# OurEDA-P1K_sensor.net
KiCad netlist of a schematic drawn in Altium Designer
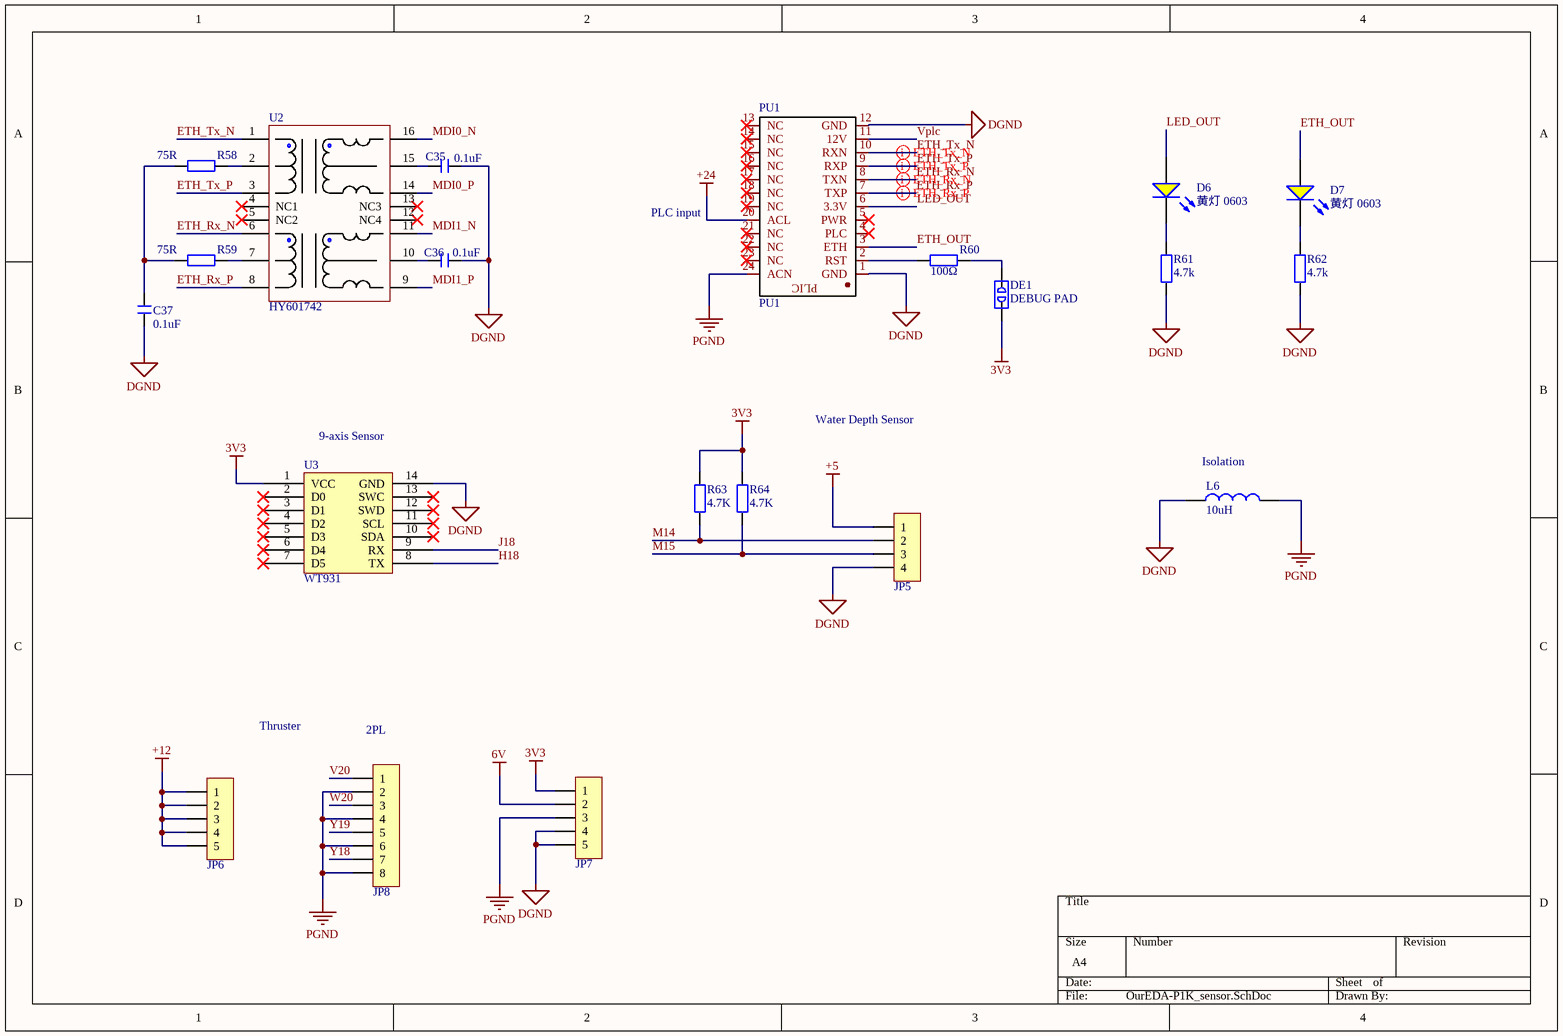
[diagram p0: OurEDA-P1K_sensor.SchDoc]

(export (version "E")
  (design (tool "Eeschema 10.0.6"))
  (components
    (comp (ref "C35")
      (value "0.1uF")
      (footprint "C 0603_L")
      (description "无极性贴片电容")
      (fields (field (name "版权归属") "源创客"))
      (libsource (lib "3.1   - 电阻-电容-电感") (part "C"))
    )
    (comp (ref "C36")
      (value "0.1uF")
      (footprint "C 0603_L")
      (description "无极性贴片电容")
      (fields (field (name "版权归属") "源创客"))
      (libsource (lib "3.1   - 电阻-电容-电感") (part "C"))
    )
    (comp (ref "C37")
      (value "0.1uF")
      (footprint "C 0603_L")
      (description "无极性贴片电容")
      (fields (field (name "版权归属") "源创客"))
      (libsource (lib "3.1   - 电阻-电容-电感") (part "C"))
    )
    (comp (ref "D6")
      (value "黄灯 0603")
      (footprint "0603_LED_S1")
      (description "发光二极管")
      (libsource (lib "Miscellaneous Devices LC") (part "0603 黄灯"))
    )
    (comp (ref "D7")
      (value "黄灯 0603")
      (footprint "0603_LED_S1")
      (description "发光二极管")
      (libsource (lib "Miscellaneous Devices LC") (part "0603 黄灯"))
    )
    (comp (ref "DE1")
      (value "DEBUG PAD")
      (footprint "DEBUG_A")
      (description "调试断点焊盘")
      (fields (field (name "版权归属") "源创客"))
      (libsource (lib "15.1 - 未分类器件") (part "DEBUG"))
    )
    (comp (ref "JP5")
      (value "HDR-1X4")
      (footprint "MX 1.25-LI-4P")
      (description "4P接插件")
      (fields (field (name "版权归属") "源创客"))
      (libsource (lib "4.2   - 接插件-脚距1.25") (part "Header 4"))
    )
    (comp (ref "JP6")
      (value "HDR-1X5")
      (footprint "KF128-5.08-5P")
      (description "5P接插件")
      (fields (field (name "版权归属") "源创客"))
      (libsource (lib "4.10 - 接插件-脚距5.08") (part "Header 5"))
    )
    (comp (ref "JP7")
      (value "HDR-1X5")
      (footprint "KF128-5.08-5P")
      (description "5P接插件")
      (fields (field (name "版权归属") "源创客"))
      (libsource (lib "4.10 - 接插件-脚距5.08") (part "Header 5"))
    )
    (comp (ref "JP8")
      (value "HDR-1X8")
      (footprint "KF128-5.08-8P")
      (description "8P接插件")
      (fields (field (name "版权归属") "源创客"))
      (libsource (lib "4.10 - 接插件-脚距5.08") (part "Header 8"))
    )
    (comp (ref "L6")
      (value "10uH")
      (footprint "L 0805")
      (description "小功率贴片电感")
      (fields (field (name "版权归属") "源创客"))
      (libsource (lib "3.1   - 电阻-电容-电感") (part "L"))
    )
    (comp (ref "PU1") (value "PU1") (footprint "LW-MPA223A") (libsource (lib "SchLib1") (part "LW-MPA223A")))
    (comp (ref "R58")
      (value "75R")
      (footprint "0603_R")
      (description "贴片电阻")
      (libsource (lib "Miscellaneous Devices LC") (part "0603 330Ω (3300) 1%"))
    )
    (comp (ref "R59")
      (value "75R")
      (footprint "0603_R")
      (description "贴片电阻")
      (libsource (lib "Miscellaneous Devices LC") (part "0603 330Ω (3300) 1%"))
    )
    (comp (ref "R60")
      (value "100Ω")
      (footprint "0603_R")
      (description "贴片电阻")
      (libsource (lib "Miscellaneous Devices LC") (part "0603 330Ω (3300) 1%"))
    )
    (comp (ref "R61")
      (value "4.7k")
      (footprint "R 0603_L")
      (description "贴片电阻")
      (fields (field (name "版权归属") "源创客"))
      (libsource (lib "3.1   - 电阻-电容-电感") (part "R"))
    )
    (comp (ref "R62")
      (value "4.7k")
      (footprint "R 0603_L")
      (description "贴片电阻")
      (fields (field (name "版权归属") "源创客"))
      (libsource (lib "3.1   - 电阻-电容-电感") (part "R"))
    )
    (comp (ref "R63")
      (value "4.7K")
      (footprint "R 0603_L")
      (description "贴片电阻")
      (fields (field (name "版权归属") "源创客"))
      (libsource (lib "3.1   - 电阻-电容-电感") (part "R"))
    )
    (comp (ref "R64")
      (value "4.7K")
      (footprint "R 0603_L")
      (description "贴片电阻")
      (fields (field (name "版权归属") "源创客"))
      (libsource (lib "3.1   - 电阻-电容-电感") (part "R"))
    )
    (comp (ref "U2")
      (value "HY601742")
      (footprint "SOP-16_350mil")
      (description "以太网变压器")
      (libsource (lib "MySchLib") (part "HY601742_1"))
    )
    (comp (ref "U3")
      (value "WT931")
      (footprint "WT931")
      (description "维特智能WT931九轴模块")
      (libsource (lib "MySchLib") (part "WT931"))
    )
  )
  (nets
    (net (code "1") (name "+5") (class "Default")
      (node (ref "JP5") (pin "1") (pinfunction "1_1") (pintype "passive"))
    )
    (net (code "2") (name "+12") (class "Default")
      (node (ref "JP6") (pin "1") (pinfunction "1_1") (pintype "passive"))
      (node (ref "JP6") (pin "2") (pinfunction "2_2") (pintype "passive"))
      (node (ref "JP6") (pin "3") (pinfunction "3_3") (pintype "passive"))
      (node (ref "JP6") (pin "4") (pinfunction "4_4") (pintype "passive"))
      (node (ref "JP6") (pin "5") (pinfunction "5_5") (pintype "passive"))
    )
    (net (code "3") (name "+24") (class "Default")
      (node (ref "PU1") (pin "20") (pinfunction "ACL_20") (pintype "passive"))
    )
    (net (code "4") (name "/ETH_OUT") (class "Default")
      (node (ref "D7") (pin "A") (pinfunction "A_A") (pintype "passive"))
      (node (ref "PU1") (pin "3") (pinfunction "ETH_3") (pintype "passive"))
    )
    (net (code "5") (name "/ETH_Rx_N") (class "Default")
      (node (ref "PU1") (pin "8") (pinfunction "TXN_8") (pintype "passive"))
      (node (ref "U2") (pin "6") (pinfunction "RD+_6") (pintype "passive"))
    )
    (net (code "6") (name "/ETH_Rx_P") (class "Default")
      (node (ref "PU1") (pin "7") (pinfunction "TXP_7") (pintype "passive"))
      (node (ref "U2") (pin "8") (pinfunction "RD-_8") (pintype "passive"))
    )
    (net (code "7") (name "/ETH_Tx_N") (class "Default")
      (node (ref "PU1") (pin "10") (pinfunction "RXN_10") (pintype "passive"))
      (node (ref "U2") (pin "1") (pinfunction "TD+_1") (pintype "passive"))
    )
    (net (code "8") (name "/ETH_Tx_P") (class "Default")
      (node (ref "PU1") (pin "9") (pinfunction "RXP_9") (pintype "passive"))
      (node (ref "U2") (pin "3") (pinfunction "TD-_3") (pintype "passive"))
    )
    (net (code "9") (name "/H18") (class "Default")
      (node (ref "U3") (pin "8") (pinfunction "TX_8") (pintype "passive"))
    )
    (net (code "10") (name "/J18") (class "Default")
      (node (ref "U3") (pin "9") (pinfunction "RX_9") (pintype "passive"))
    )
    (net (code "11") (name "/LED_OUT") (class "Default")
      (node (ref "D6") (pin "A") (pinfunction "A_A") (pintype "passive"))
      (node (ref "PU1") (pin "6") (pinfunction "3.3V_6") (pintype "passive"))
    )
    (net (code "12") (name "/M14") (class "Default")
      (node (ref "JP5") (pin "2") (pinfunction "2_2") (pintype "passive"))
      (node (ref "R63") (pin "1") (pinfunction "1_1") (pintype "passive"))
    )
    (net (code "13") (name "/M15") (class "Default")
      (node (ref "JP5") (pin "3") (pinfunction "3_3") (pintype "passive"))
      (node (ref "R64") (pin "1") (pinfunction "1_1") (pintype "passive"))
    )
    (net (code "14") (name "/MDI0_N") (class "Default")
      (node (ref "U2") (pin "16") (pinfunction "TX+_16") (pintype "passive"))
    )
    (net (code "15") (name "/MDI0_P") (class "Default")
      (node (ref "U2") (pin "14") (pinfunction "TX-_14") (pintype "passive"))
    )
    (net (code "16") (name "/MDI1_N") (class "Default")
      (node (ref "U2") (pin "11") (pinfunction "RX+_11") (pintype "passive"))
    )
    (net (code "17") (name "/MDI1_P") (class "Default")
      (node (ref "U2") (pin "9") (pinfunction "RX-_9") (pintype "passive"))
    )
    (net (code "18") (name "/V20") (class "Default")
      (node (ref "JP8") (pin "1") (pinfunction "1_1") (pintype "passive"))
    )
    (net (code "19") (name "/Vplc") (class "Default")
      (node (ref "PU1") (pin "11") (pinfunction "12V_11") (pintype "passive"))
    )
    (net (code "20") (name "/W20") (class "Default")
      (node (ref "JP8") (pin "3") (pinfunction "3_3") (pintype "passive"))
    )
    (net (code "21") (name "/Y18") (class "Default")
      (node (ref "JP8") (pin "7") (pinfunction "7_7") (pintype "passive"))
    )
    (net (code "22") (name "/Y19") (class "Default")
      (node (ref "JP8") (pin "5") (pinfunction "5_5") (pintype "passive"))
    )
    (net (code "23") (name "3V3") (class "Default")
      (node (ref "DE1") (pin "1") (pinfunction "1_1") (pintype "passive"))
      (node (ref "JP7") (pin "1") (pinfunction "1_1") (pintype "passive"))
      (node (ref "R63") (pin "2") (pinfunction "2_2") (pintype "passive"))
      (node (ref "R64") (pin "2") (pinfunction "2_2") (pintype "passive"))
      (node (ref "U3") (pin "1") (pinfunction "VCC_1") (pintype "passive"))
    )
    (net (code "24") (name "6V") (class "Default")
      (node (ref "JP7") (pin "2") (pinfunction "2_2") (pintype "passive"))
    )
    (net (code "25") (name "DGND") (class "Default")
      (node (ref "C35") (pin "1") (pinfunction "1_1") (pintype "passive"))
      (node (ref "C36") (pin "1") (pinfunction "1_1") (pintype "passive"))
      (node (ref "C37") (pin "1") (pinfunction "1_1") (pintype "passive"))
      (node (ref "JP5") (pin "4") (pinfunction "4_4") (pintype "passive"))
      (node (ref "JP7") (pin "4") (pinfunction "4_4") (pintype "passive"))
      (node (ref "JP7") (pin "5") (pinfunction "5_5") (pintype "passive"))
      (node (ref "L6") (pin "1") (pinfunction "1_1") (pintype "passive"))
      (node (ref "PU1") (pin "1") (pinfunction "GND_1") (pintype "passive"))
      (node (ref "PU1") (pin "12") (pinfunction "GND_12") (pintype "passive"))
      (node (ref "R61") (pin "1") (pinfunction "1_1") (pintype "passive"))
      (node (ref "R62") (pin "1") (pinfunction "1_1") (pintype "passive"))
      (node (ref "U3") (pin "14") (pinfunction "GND_14") (pintype "passive"))
    )
    (net (code "26") (name "Net-(C37-Pad2)") (class "Default")
      (node (ref "C37") (pin "2") (pinfunction "2_2") (pintype "passive"))
      (node (ref "R58") (pin "2") (pinfunction "2_2") (pintype "passive"))
      (node (ref "R59") (pin "2") (pinfunction "2_2") (pintype "passive"))
    )
    (net (code "27") (name "Net-(D6-PadK)") (class "Default")
      (node (ref "D6") (pin "K") (pinfunction "K_K") (pintype "passive"))
      (node (ref "R61") (pin "2") (pinfunction "2_2") (pintype "passive"))
    )
    (net (code "28") (name "Net-(D7-PadK)") (class "Default")
      (node (ref "D7") (pin "K") (pinfunction "K_K") (pintype "passive"))
      (node (ref "R62") (pin "2") (pinfunction "2_2") (pintype "passive"))
    )
    (net (code "29") (name "Net-(DE1-Pad2)") (class "Default")
      (node (ref "DE1") (pin "2") (pinfunction "2_2") (pintype "passive"))
      (node (ref "R60") (pin "1") (pinfunction "1_1") (pintype "passive"))
    )
    (net (code "30") (name "Net-(PU1-RST)") (class "Default")
      (node (ref "PU1") (pin "2") (pinfunction "RST_2") (pintype "passive"))
      (node (ref "R60") (pin "2") (pinfunction "2_2") (pintype "passive"))
    )
    (net (code "31") (name "Net-(U2-CM1)") (class "Default")
      (node (ref "C35") (pin "2") (pinfunction "2_2") (pintype "passive"))
      (node (ref "U2") (pin "15") (pinfunction "CM1_15") (pintype "passive"))
    )
    (net (code "32") (name "Net-(U2-CM2)") (class "Default")
      (node (ref "C36") (pin "2") (pinfunction "2_2") (pintype "passive"))
      (node (ref "U2") (pin "10") (pinfunction "CM2_10") (pintype "passive"))
    )
    (net (code "33") (name "Net-(U2-CT1)") (class "Default")
      (node (ref "R58") (pin "1") (pinfunction "1_1") (pintype "passive"))
      (node (ref "U2") (pin "2") (pinfunction "CT1_2") (pintype "passive"))
    )
    (net (code "34") (name "Net-(U2-CT2)") (class "Default")
      (node (ref "R59") (pin "1") (pinfunction "1_1") (pintype "passive"))
      (node (ref "U2") (pin "7") (pinfunction "CT2_7") (pintype "passive"))
    )
    (net (code "35") (name "PGND") (class "Default")
      (node (ref "JP7") (pin "3") (pinfunction "3_3") (pintype "passive"))
      (node (ref "JP8") (pin "2") (pinfunction "2_2") (pintype "passive"))
      (node (ref "JP8") (pin "4") (pinfunction "4_4") (pintype "passive"))
      (node (ref "JP8") (pin "6") (pinfunction "6_6") (pintype "passive"))
      (node (ref "JP8") (pin "8") (pinfunction "8_8") (pintype "passive"))
      (node (ref "L6") (pin "2") (pinfunction "2_2") (pintype "passive"))
      (node (ref "PU1") (pin "24") (pinfunction "ACN_24") (pintype "passive"))
    )
    (net (code "36") (name "unconnected-(PU1-NC-Pad13)") (class "Default")
      (node (ref "PU1") (pin "13") (pinfunction "NC_13") (pintype "passive+no_connect"))
    )
    (net (code "37") (name "unconnected-(PU1-NC-Pad14)") (class "Default")
      (node (ref "PU1") (pin "14") (pinfunction "NC_14") (pintype "passive+no_connect"))
    )
    (net (code "38") (name "unconnected-(PU1-NC-Pad15)") (class "Default")
      (node (ref "PU1") (pin "15") (pinfunction "NC_15") (pintype "passive+no_connect"))
    )
    (net (code "39") (name "unconnected-(PU1-NC-Pad16)") (class "Default")
      (node (ref "PU1") (pin "16") (pinfunction "NC_16") (pintype "passive+no_connect"))
    )
    (net (code "40") (name "unconnected-(PU1-NC-Pad17)") (class "Default")
      (node (ref "PU1") (pin "17") (pinfunction "NC_17") (pintype "passive+no_connect"))
    )
    (net (code "41") (name "unconnected-(PU1-NC-Pad18)") (class "Default")
      (node (ref "PU1") (pin "18") (pinfunction "NC_18") (pintype "passive+no_connect"))
    )
    (net (code "42") (name "unconnected-(PU1-NC-Pad19)") (class "Default")
      (node (ref "PU1") (pin "19") (pinfunction "NC_19") (pintype "passive+no_connect"))
    )
    (net (code "43") (name "unconnected-(PU1-NC-Pad21)") (class "Default")
      (node (ref "PU1") (pin "21") (pinfunction "NC_21") (pintype "passive+no_connect"))
    )
    (net (code "44") (name "unconnected-(PU1-NC-Pad22)") (class "Default")
      (node (ref "PU1") (pin "22") (pinfunction "NC_22") (pintype "passive+no_connect"))
    )
    (net (code "45") (name "unconnected-(PU1-NC-Pad23)") (class "Default")
      (node (ref "PU1") (pin "23") (pinfunction "NC_23") (pintype "passive+no_connect"))
    )
    (net (code "46") (name "unconnected-(PU1-PLC-Pad4)") (class "Default")
      (node (ref "PU1") (pin "4") (pinfunction "PLC_4") (pintype "passive+no_connect"))
    )
    (net (code "47") (name "unconnected-(PU1-PWR-Pad5)") (class "Default")
      (node (ref "PU1") (pin "5") (pinfunction "PWR_5") (pintype "passive+no_connect"))
    )
    (net (code "48") (name "unconnected-(U2-NC1-Pad4)") (class "Default")
      (node (ref "U2") (pin "4") (pinfunction "NC1_4") (pintype "passive+no_connect"))
    )
    (net (code "49") (name "unconnected-(U2-NC2-Pad5)") (class "Default")
      (node (ref "U2") (pin "5") (pinfunction "NC2_5") (pintype "passive+no_connect"))
    )
    (net (code "50") (name "unconnected-(U2-NC3-Pad13)") (class "Default")
      (node (ref "U2") (pin "13") (pinfunction "NC3_13") (pintype "passive+no_connect"))
    )
    (net (code "51") (name "unconnected-(U2-NC4-Pad12)") (class "Default")
      (node (ref "U2") (pin "12") (pinfunction "NC4_12") (pintype "passive+no_connect"))
    )
    (net (code "52") (name "unconnected-(U3-D0-Pad2)") (class "Default")
      (node (ref "U3") (pin "2") (pinfunction "D0_2") (pintype "passive+no_connect"))
    )
    (net (code "53") (name "unconnected-(U3-D1-Pad3)") (class "Default")
      (node (ref "U3") (pin "3") (pinfunction "D1_3") (pintype "passive+no_connect"))
    )
    (net (code "54") (name "unconnected-(U3-D2-Pad4)") (class "Default")
      (node (ref "U3") (pin "4") (pinfunction "D2_4") (pintype "passive+no_connect"))
    )
    (net (code "55") (name "unconnected-(U3-D3-Pad5)") (class "Default")
      (node (ref "U3") (pin "5") (pinfunction "D3_5") (pintype "passive+no_connect"))
    )
    (net (code "56") (name "unconnected-(U3-D4-Pad6)") (class "Default")
      (node (ref "U3") (pin "6") (pinfunction "D4_6") (pintype "passive+no_connect"))
    )
    (net (code "57") (name "unconnected-(U3-D5-Pad7)") (class "Default")
      (node (ref "U3") (pin "7") (pinfunction "D5_7") (pintype "passive+no_connect"))
    )
    (net (code "58") (name "unconnected-(U3-SCL-Pad11)") (class "Default")
      (node (ref "U3") (pin "11") (pinfunction "SCL_11") (pintype "passive+no_connect"))
    )
    (net (code "59") (name "unconnected-(U3-SDA-Pad10)") (class "Default")
      (node (ref "U3") (pin "10") (pinfunction "SDA_10") (pintype "passive+no_connect"))
    )
    (net (code "60") (name "unconnected-(U3-SWC-Pad13)") (class "Default")
      (node (ref "U3") (pin "13") (pinfunction "SWC_13") (pintype "passive+no_connect"))
    )
    (net (code "61") (name "unconnected-(U3-SWD-Pad12)") (class "Default")
      (node (ref "U3") (pin "12") (pinfunction "SWD_12") (pintype "passive+no_connect"))
    )
  )
)
